# BLDC_driver_2020-06-03_09-24-41.net
KiCad netlist of a schematic drawn in EasyEDA
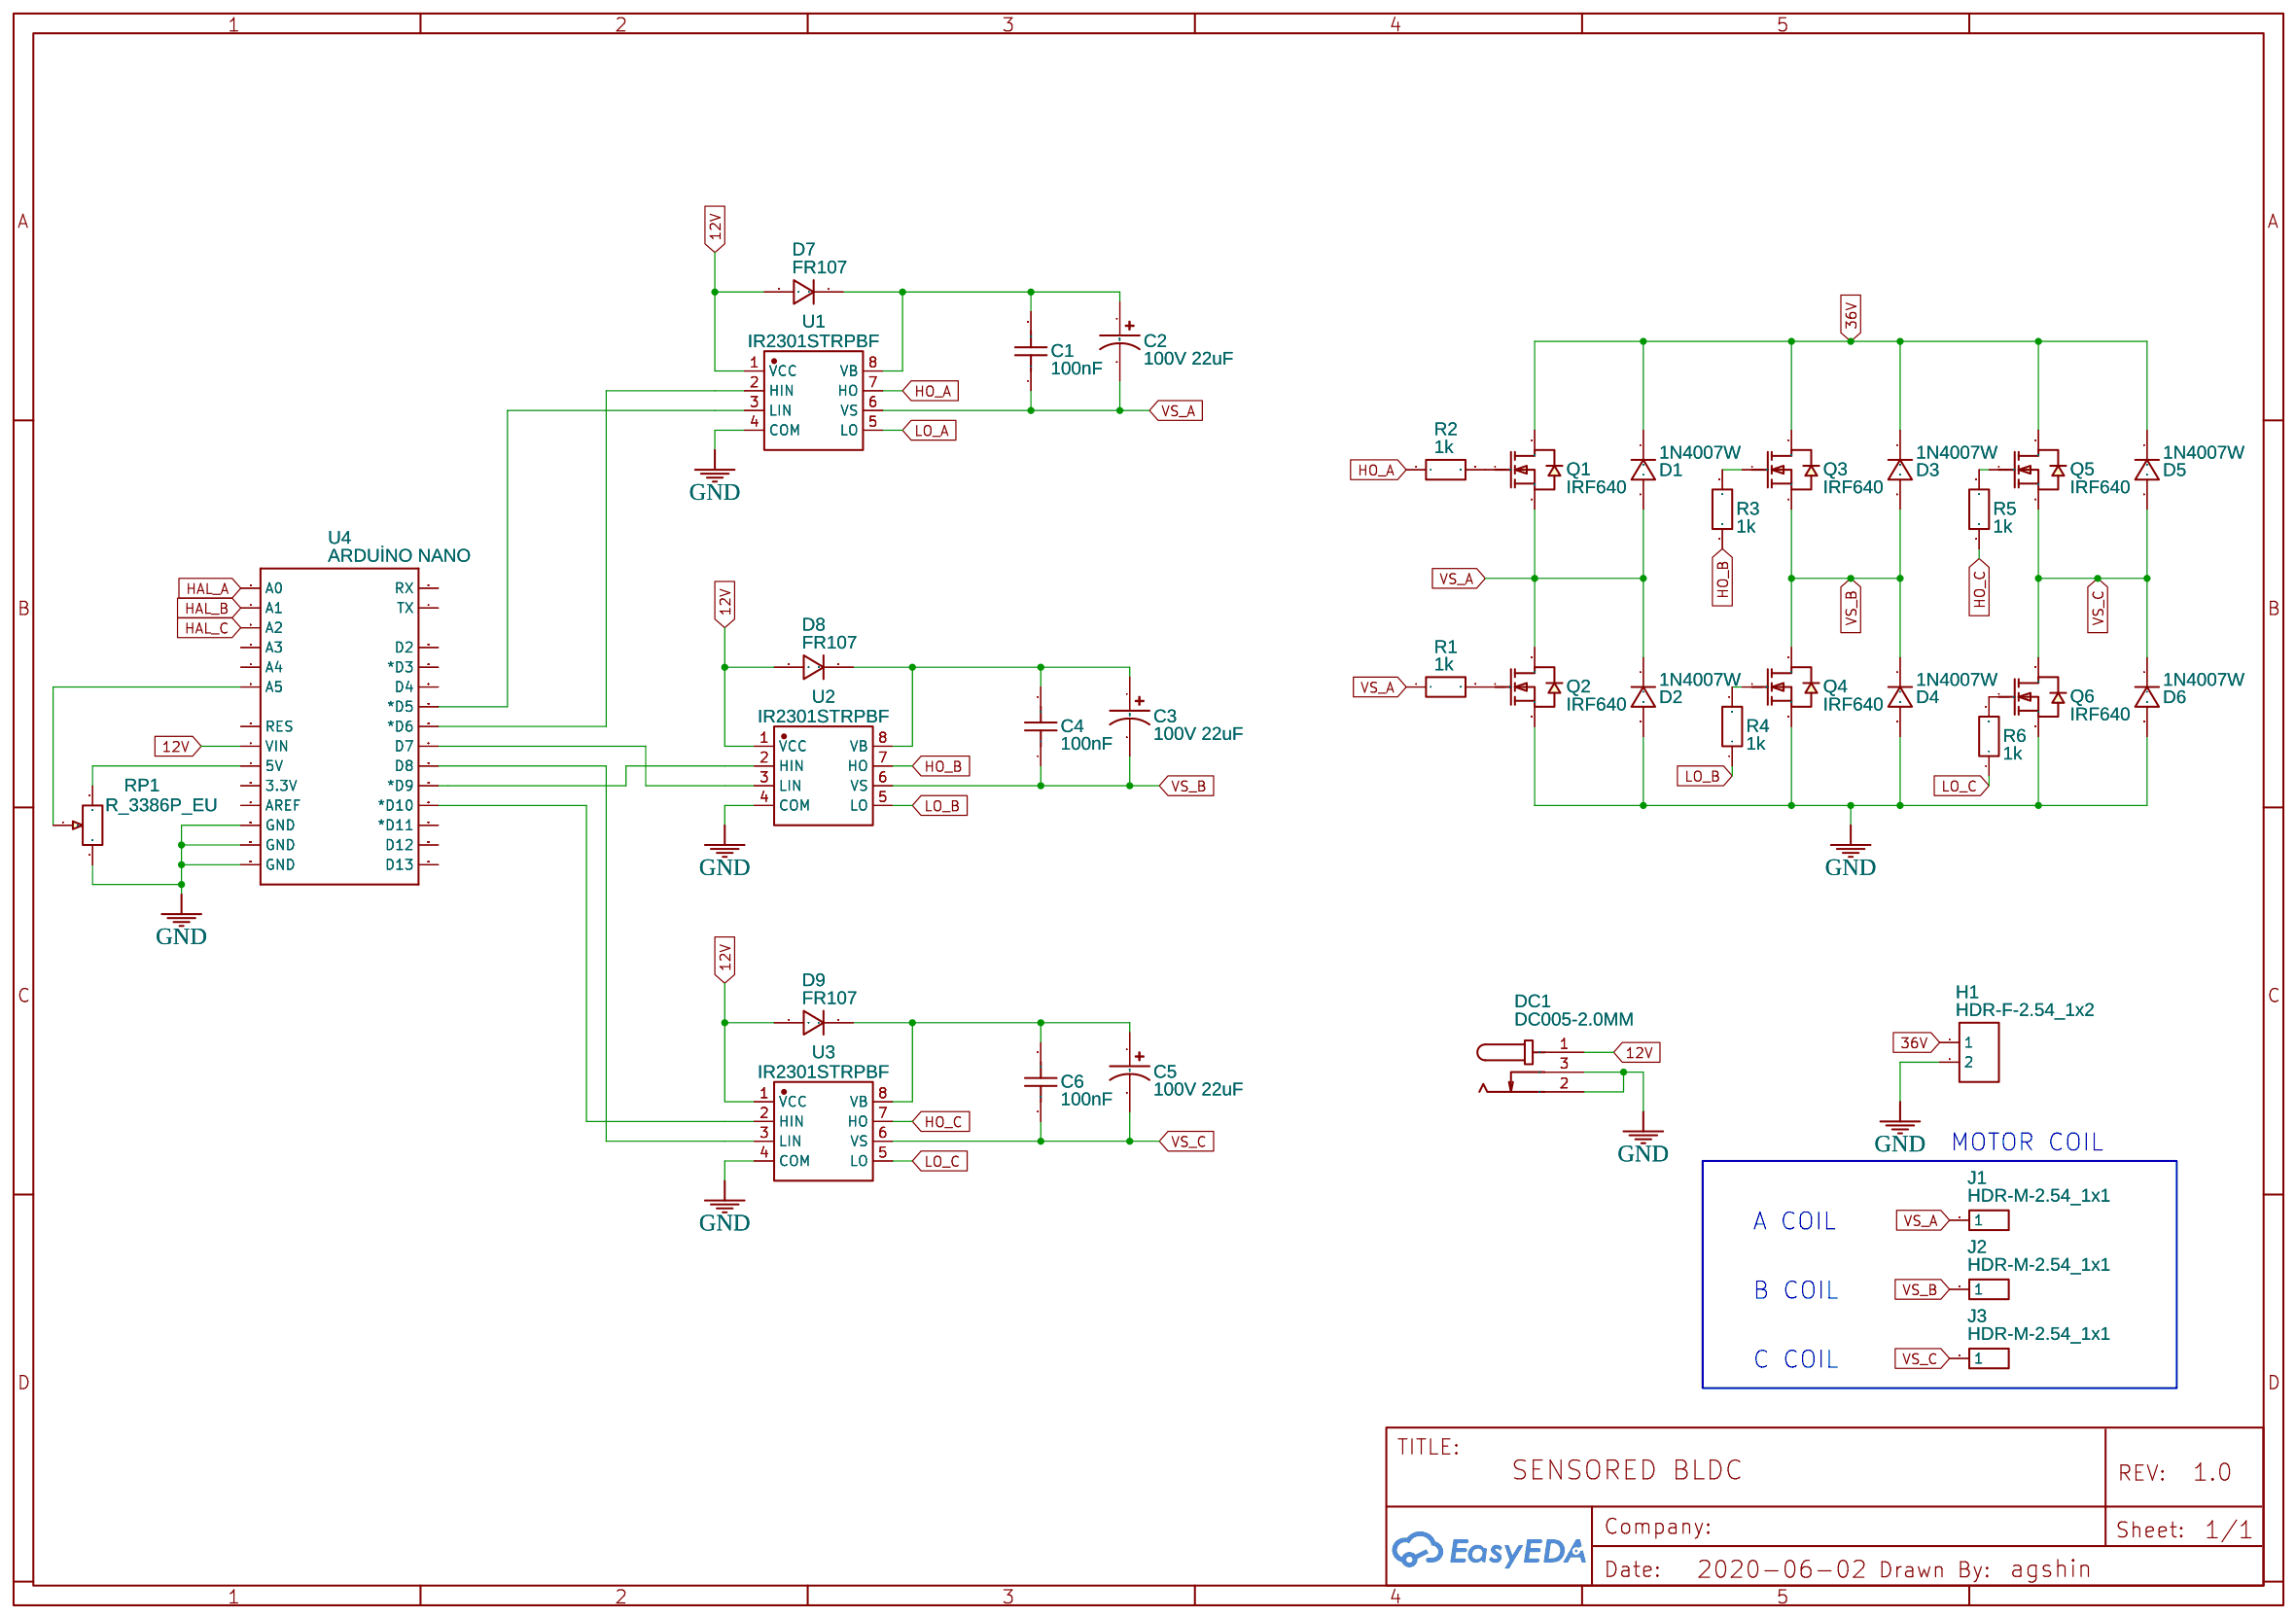
[diagram p0: schematic sheet]

(export (version "E")
  (design (tool "Eeschema 10.0.6"))
  (components
    (comp (ref "C1") (value "100nF") (libsource (lib "") (part "C_0201_US")))
    (comp (ref "C2") (value "100V 22uF") (libsource (lib "") (part "C_Tan_SMD_A_US")))
    (comp (ref "C3") (value "100V 22uF") (libsource (lib "") (part "C_Tan_SMD_A_US")))
    (comp (ref "C4") (value "100nF") (libsource (lib "") (part "C_0201_US")))
    (comp (ref "C5") (value "100V 22uF") (libsource (lib "") (part "C_Tan_SMD_A_US")))
    (comp (ref "C6") (value "100nF") (libsource (lib "") (part "C_0201_US")))
    (comp (ref "D1")
      (value "1N4007W")
      (fields (field (name "BOM_Supplier Part") "C328592"))
      (libsource (lib "") (part "1N4007W"))
    )
    (comp (ref "D2")
      (value "1N4007W")
      (fields (field (name "BOM_Supplier Part") "C328592"))
      (libsource (lib "") (part "1N4007W"))
    )
    (comp (ref "D3")
      (value "1N4007W")
      (fields (field (name "BOM_Supplier Part") "C328592"))
      (libsource (lib "") (part "1N4007W"))
    )
    (comp (ref "D4")
      (value "1N4007W")
      (fields (field (name "BOM_Supplier Part") "C328592"))
      (libsource (lib "") (part "1N4007W"))
    )
    (comp (ref "D5")
      (value "1N4007W")
      (fields (field (name "BOM_Supplier Part") "C328592"))
      (libsource (lib "") (part "1N4007W"))
    )
    (comp (ref "D6")
      (value "1N4007W")
      (fields (field (name "BOM_Supplier Part") "C328592"))
      (libsource (lib "") (part "1N4007W"))
    )
    (comp (ref "D7")
      (value "FR107")
      (fields (field (name "BOM_Manufacturer Part") "1N4007W") (field (name "BOM_Supplier Part") "C328592"))
      (libsource (lib "") (part "1N4007W_1"))
    )
    (comp (ref "D8")
      (value "FR107")
      (fields (field (name "BOM_Manufacturer Part") "1N4007W") (field (name "BOM_Supplier Part") "C328592"))
      (libsource (lib "") (part "1N4007W_1"))
    )
    (comp (ref "D9")
      (value "FR107")
      (fields (field (name "BOM_Manufacturer Part") "1N4007W") (field (name "BOM_Supplier Part") "C328592"))
      (libsource (lib "") (part "1N4007W_1"))
    )
    (comp (ref "DC1")
      (value "DC005-2.0MM")
      (fields (field (name "BOM_Supplier Part") "C111567"))
      (libsource (lib "") (part "DC005-2.0MM"))
    )
    (comp (ref "H1")
      (value "HDR-F-2.54_1x2")
      (fields (field (name "BOM_Supplier Part") "C49661"))
      (libsource (lib "") (part "HDR-F-2.54_1x2"))
    )
    (comp (ref "J1")
      (value "HDR-M-2.54_1x1")
      (fields (field (name "BOM_Supplier Part") "C81276"))
      (libsource (lib "") (part "HDR-M-2.54_1x1"))
    )
    (comp (ref "J2")
      (value "HDR-M-2.54_1x1")
      (fields (field (name "BOM_Supplier Part") "C81276"))
      (libsource (lib "") (part "HDR-M-2.54_1x1"))
    )
    (comp (ref "J3")
      (value "HDR-M-2.54_1x1")
      (fields (field (name "BOM_Supplier Part") "C81276"))
      (libsource (lib "") (part "HDR-M-2.54_1x1"))
    )
    (comp (ref "Q1")
      (value "IRF640")
      (fields (field (name "BOM_Manufacturer Part") "2N7002,215") (field (name "BOM_Supplier Part") "C65189"))
      (libsource (lib "") (part "2N7002"))
    )
    (comp (ref "Q2")
      (value "IRF640")
      (fields (field (name "BOM_Manufacturer Part") "2N7002,215") (field (name "BOM_Supplier Part") "C65189"))
      (libsource (lib "") (part "2N7002"))
    )
    (comp (ref "Q3")
      (value "IRF640")
      (fields (field (name "BOM_Manufacturer Part") "2N7002,215") (field (name "BOM_Supplier Part") "C65189"))
      (libsource (lib "") (part "2N7002"))
    )
    (comp (ref "Q4")
      (value "IRF640")
      (fields (field (name "BOM_Manufacturer Part") "2N7002,215") (field (name "BOM_Supplier Part") "C65189"))
      (libsource (lib "") (part "2N7002"))
    )
    (comp (ref "Q5")
      (value "IRF640")
      (fields (field (name "BOM_Manufacturer Part") "2N7002,215") (field (name "BOM_Supplier Part") "C65189"))
      (libsource (lib "") (part "2N7002"))
    )
    (comp (ref "Q6")
      (value "IRF640")
      (fields (field (name "BOM_Manufacturer Part") "2N7002,215") (field (name "BOM_Supplier Part") "C65189"))
      (libsource (lib "") (part "2N7002"))
    )
    (comp (ref "R1") (value "1k") (libsource (lib "") (part "R_0201_EU_1")))
    (comp (ref "R2") (value "1k") (libsource (lib "") (part "R_0201_EU_1")))
    (comp (ref "R3") (value "1k") (libsource (lib "") (part "R_0201_EU")))
    (comp (ref "R4") (value "1k") (libsource (lib "") (part "R_0201_EU")))
    (comp (ref "R5") (value "1k") (libsource (lib "") (part "R_0201_EU")))
    (comp (ref "R6") (value "1k") (libsource (lib "") (part "R_0201_EU")))
    (comp (ref "RP1") (value "R_3386P_EU") (libsource (lib "") (part "R_3386P_EU")))
    (comp (ref "U1")
      (value "IR2301STRPBF")
      (fields (field (name "BOM_Supplier Part") "C413500"))
      (libsource (lib "") (part "IR2301STRPBF"))
    )
    (comp (ref "U2")
      (value "IR2301STRPBF")
      (fields (field (name "BOM_Supplier Part") "C413500"))
      (libsource (lib "") (part "IR2301STRPBF"))
    )
    (comp (ref "U3")
      (value "IR2301STRPBF")
      (fields (field (name "BOM_Supplier Part") "C413500"))
      (libsource (lib "") (part "IR2301STRPBF"))
    )
    (comp (ref "U4") (value "ARDUİNO NANO") (libsource (lib "") (part "ARDUINO_SHIELDNO_SILK")))
  )
  (nets
    (net (code "1") (name "12V") (class "Default")
      (node (ref "D7") (pin "2") (pinfunction "2_2") (pintype "unspecified"))
      (node (ref "D8") (pin "2") (pinfunction "2_2") (pintype "unspecified"))
      (node (ref "D9") (pin "2") (pinfunction "2_2") (pintype "unspecified"))
      (node (ref "DC1") (pin "1") (pinfunction "1_1") (pintype "unspecified"))
      (node (ref "U1") (pin "1") (pinfunction "VCC_1") (pintype "unspecified"))
      (node (ref "U2") (pin "1") (pinfunction "VCC_1") (pintype "unspecified"))
      (node (ref "U3") (pin "1") (pinfunction "VCC_1") (pintype "unspecified"))
      (node (ref "U4") (pin "VIN") (pinfunction "VIN_VIN") (pintype "unspecified"))
    )
    (net (code "2") (name "36V") (class "Default")
      (node (ref "D1") (pin "1") (pinfunction "1_1") (pintype "unspecified"))
      (node (ref "D3") (pin "1") (pinfunction "1_1") (pintype "unspecified"))
      (node (ref "D5") (pin "1") (pinfunction "1_1") (pintype "unspecified"))
      (node (ref "H1") (pin "1") (pinfunction "1_1") (pintype "input"))
      (node (ref "Q1") (pin "3") (pinfunction "D_3") (pintype "unspecified"))
      (node (ref "Q3") (pin "3") (pinfunction "D_3") (pintype "unspecified"))
      (node (ref "Q5") (pin "3") (pinfunction "D_3") (pintype "unspecified"))
    )
    (net (code "3") (name "GND") (class "Default")
      (node (ref "D2") (pin "2") (pinfunction "2_2") (pintype "unspecified"))
      (node (ref "D4") (pin "2") (pinfunction "2_2") (pintype "unspecified"))
      (node (ref "D6") (pin "2") (pinfunction "2_2") (pintype "unspecified"))
      (node (ref "DC1") (pin "2") (pinfunction "2_2") (pintype "unspecified"))
      (node (ref "DC1") (pin "3") (pinfunction "3_3") (pintype "unspecified"))
      (node (ref "H1") (pin "2") (pinfunction "2_2") (pintype "input"))
      (node (ref "Q2") (pin "2") (pinfunction "S_2") (pintype "unspecified"))
      (node (ref "Q4") (pin "2") (pinfunction "S_2") (pintype "unspecified"))
      (node (ref "Q6") (pin "2") (pinfunction "S_2") (pintype "unspecified"))
      (node (ref "RP1") (pin "1") (pinfunction "1_1") (pintype "input"))
      (node (ref "U1") (pin "4") (pinfunction "COM_4") (pintype "unspecified"))
      (node (ref "U2") (pin "4") (pinfunction "COM_4") (pintype "unspecified"))
      (node (ref "U3") (pin "4") (pinfunction "COM_4") (pintype "unspecified"))
      (node (ref "U4") (pin "GND@0") (pinfunction "GND_GND@0") (pintype "unspecified"))
      (node (ref "U4") (pin "GND@1") (pinfunction "GND_GND@1") (pintype "unspecified"))
      (node (ref "U4") (pin "GND@2") (pinfunction "GND_GND@2") (pintype "unspecified"))
    )
    (net (code "4") (name "HAL_A") (class "Default")
      (node (ref "U4") (pin "A0") (pinfunction "A0_A0") (pintype "unspecified"))
    )
    (net (code "5") (name "HAL_B") (class "Default")
      (node (ref "U4") (pin "A1") (pinfunction "A1_A1") (pintype "unspecified"))
    )
    (net (code "6") (name "HAL_C") (class "Default")
      (node (ref "U4") (pin "A2") (pinfunction "A2_A2") (pintype "unspecified"))
    )
    (net (code "7") (name "HO_A") (class "Default")
      (node (ref "R2") (pin "1") (pinfunction "1_1") (pintype "unspecified"))
      (node (ref "U1") (pin "7") (pinfunction "HO_7") (pintype "unspecified"))
    )
    (net (code "8") (name "HO_B") (class "Default")
      (node (ref "R3") (pin "1") (pinfunction "1_1") (pintype "unspecified"))
      (node (ref "U2") (pin "7") (pinfunction "HO_7") (pintype "unspecified"))
    )
    (net (code "9") (name "HO_C") (class "Default")
      (node (ref "R5") (pin "1") (pinfunction "1_1") (pintype "unspecified"))
      (node (ref "U3") (pin "7") (pinfunction "HO_7") (pintype "unspecified"))
    )
    (net (code "10") (name "LO_A") (class "Default")
      (node (ref "U1") (pin "5") (pinfunction "LO_5") (pintype "unspecified"))
    )
    (net (code "11") (name "LO_B") (class "Default")
      (node (ref "R4") (pin "1") (pinfunction "1_1") (pintype "unspecified"))
      (node (ref "U2") (pin "5") (pinfunction "LO_5") (pintype "unspecified"))
    )
    (net (code "12") (name "LO_C") (class "Default")
      (node (ref "R6") (pin "1") (pinfunction "1_1") (pintype "unspecified"))
      (node (ref "U3") (pin "5") (pinfunction "LO_5") (pintype "unspecified"))
    )
    (net (code "13") (name "Net-(Q1-G)") (class "Default")
      (node (ref "Q1") (pin "1") (pinfunction "G_1") (pintype "unspecified"))
      (node (ref "R2") (pin "2") (pinfunction "2_2") (pintype "unspecified"))
    )
    (net (code "14") (name "Net-(Q2-G)") (class "Default")
      (node (ref "Q2") (pin "1") (pinfunction "G_1") (pintype "unspecified"))
      (node (ref "R1") (pin "2") (pinfunction "2_2") (pintype "unspecified"))
    )
    (net (code "15") (name "Net-(Q3-G)") (class "Default")
      (node (ref "Q3") (pin "1") (pinfunction "G_1") (pintype "unspecified"))
      (node (ref "R3") (pin "2") (pinfunction "2_2") (pintype "unspecified"))
    )
    (net (code "16") (name "Net-(Q4-G)") (class "Default")
      (node (ref "Q4") (pin "1") (pinfunction "G_1") (pintype "unspecified"))
      (node (ref "R4") (pin "2") (pinfunction "2_2") (pintype "unspecified"))
    )
    (net (code "17") (name "Net-(Q5-G)") (class "Default")
      (node (ref "Q5") (pin "1") (pinfunction "G_1") (pintype "unspecified"))
      (node (ref "R5") (pin "2") (pinfunction "2_2") (pintype "unspecified"))
    )
    (net (code "18") (name "Net-(Q6-G)") (class "Default")
      (node (ref "Q6") (pin "1") (pinfunction "G_1") (pintype "unspecified"))
      (node (ref "R6") (pin "2") (pinfunction "2_2") (pintype "unspecified"))
    )
    (net (code "19") (name "Net-(RP1-Pad2)") (class "Default")
      (node (ref "RP1") (pin "2") (pinfunction "2_2") (pintype "input"))
      (node (ref "U4") (pin "A5") (pinfunction "A5_A5") (pintype "unspecified"))
    )
    (net (code "20") (name "Net-(RP1-Pad3)") (class "Default")
      (node (ref "RP1") (pin "3") (pinfunction "3_3") (pintype "input"))
      (node (ref "U4") (pin "5V") (pinfunction "5V_5V") (pintype "unspecified"))
    )
    (net (code "21") (name "Net-(U1-HIN)") (class "Default")
      (node (ref "U1") (pin "2") (pinfunction "HIN_2") (pintype "unspecified"))
      (node (ref "U4") (pin "D6") (pinfunction "*D6_D6") (pintype "unspecified"))
    )
    (net (code "22") (name "Net-(U1-LIN)") (class "Default")
      (node (ref "U1") (pin "3") (pinfunction "LIN_3") (pintype "unspecified"))
      (node (ref "U4") (pin "D5") (pinfunction "*D5_D5") (pintype "unspecified"))
    )
    (net (code "23") (name "Net-(U1-VB)") (class "Default")
      (node (ref "C1") (pin "2") (pinfunction "2_2") (pintype "unspecified"))
      (node (ref "C2") (pin "1") (pinfunction "1_1") (pintype "unspecified"))
      (node (ref "D7") (pin "1") (pinfunction "1_1") (pintype "unspecified"))
      (node (ref "U1") (pin "8") (pinfunction "VB_8") (pintype "unspecified"))
    )
    (net (code "24") (name "Net-(U2-HIN)") (class "Default")
      (node (ref "U2") (pin "2") (pinfunction "HIN_2") (pintype "unspecified"))
      (node (ref "U4") (pin "D9") (pinfunction "*D9_D9") (pintype "unspecified"))
    )
    (net (code "25") (name "Net-(U2-LIN)") (class "Default")
      (node (ref "U2") (pin "3") (pinfunction "LIN_3") (pintype "unspecified"))
      (node (ref "U4") (pin "D7") (pinfunction "D7_D7") (pintype "unspecified"))
    )
    (net (code "26") (name "Net-(U2-VB)") (class "Default")
      (node (ref "C3") (pin "1") (pinfunction "1_1") (pintype "unspecified"))
      (node (ref "C4") (pin "2") (pinfunction "2_2") (pintype "unspecified"))
      (node (ref "D8") (pin "1") (pinfunction "1_1") (pintype "unspecified"))
      (node (ref "U2") (pin "8") (pinfunction "VB_8") (pintype "unspecified"))
    )
    (net (code "27") (name "Net-(U3-HIN)") (class "Default")
      (node (ref "U3") (pin "2") (pinfunction "HIN_2") (pintype "unspecified"))
      (node (ref "U4") (pin "D10") (pinfunction "*D10_D10") (pintype "unspecified"))
    )
    (net (code "28") (name "Net-(U3-LIN)") (class "Default")
      (node (ref "U3") (pin "3") (pinfunction "LIN_3") (pintype "unspecified"))
      (node (ref "U4") (pin "D8") (pinfunction "D8_D8") (pintype "unspecified"))
    )
    (net (code "29") (name "Net-(U3-VB)") (class "Default")
      (node (ref "C5") (pin "1") (pinfunction "1_1") (pintype "unspecified"))
      (node (ref "C6") (pin "2") (pinfunction "2_2") (pintype "unspecified"))
      (node (ref "D9") (pin "1") (pinfunction "1_1") (pintype "unspecified"))
      (node (ref "U3") (pin "8") (pinfunction "VB_8") (pintype "unspecified"))
    )
    (net (code "30") (name "VS_A") (class "Default")
      (node (ref "C1") (pin "1") (pinfunction "1_1") (pintype "unspecified"))
      (node (ref "C2") (pin "2") (pinfunction "2_2") (pintype "unspecified"))
      (node (ref "D1") (pin "2") (pinfunction "2_2") (pintype "unspecified"))
      (node (ref "D2") (pin "1") (pinfunction "1_1") (pintype "unspecified"))
      (node (ref "J1") (pin "1") (pinfunction "1_1") (pintype "input"))
      (node (ref "Q1") (pin "2") (pinfunction "S_2") (pintype "unspecified"))
      (node (ref "Q2") (pin "3") (pinfunction "D_3") (pintype "unspecified"))
      (node (ref "R1") (pin "1") (pinfunction "1_1") (pintype "unspecified"))
      (node (ref "U1") (pin "6") (pinfunction "VS_6") (pintype "unspecified"))
    )
    (net (code "31") (name "VS_B") (class "Default")
      (node (ref "C3") (pin "2") (pinfunction "2_2") (pintype "unspecified"))
      (node (ref "C4") (pin "1") (pinfunction "1_1") (pintype "unspecified"))
      (node (ref "D3") (pin "2") (pinfunction "2_2") (pintype "unspecified"))
      (node (ref "D4") (pin "1") (pinfunction "1_1") (pintype "unspecified"))
      (node (ref "J2") (pin "1") (pinfunction "1_1") (pintype "input"))
      (node (ref "Q3") (pin "2") (pinfunction "S_2") (pintype "unspecified"))
      (node (ref "Q4") (pin "3") (pinfunction "D_3") (pintype "unspecified"))
      (node (ref "U2") (pin "6") (pinfunction "VS_6") (pintype "unspecified"))
    )
    (net (code "32") (name "VS_C") (class "Default")
      (node (ref "C5") (pin "2") (pinfunction "2_2") (pintype "unspecified"))
      (node (ref "C6") (pin "1") (pinfunction "1_1") (pintype "unspecified"))
      (node (ref "D5") (pin "2") (pinfunction "2_2") (pintype "unspecified"))
      (node (ref "D6") (pin "1") (pinfunction "1_1") (pintype "unspecified"))
      (node (ref "J3") (pin "1") (pinfunction "1_1") (pintype "input"))
      (node (ref "Q5") (pin "2") (pinfunction "S_2") (pintype "unspecified"))
      (node (ref "Q6") (pin "3") (pinfunction "D_3") (pintype "unspecified"))
      (node (ref "U3") (pin "6") (pinfunction "VS_6") (pintype "unspecified"))
    )
    (net (code "33") (name "unconnected-(U4-*D3-PadD3)") (class "Default")
      (node (ref "U4") (pin "D3") (pinfunction "*D3_D3") (pintype "unspecified"))
    )
    (net (code "34") (name "unconnected-(U4-*D11-PadD11)") (class "Default")
      (node (ref "U4") (pin "D11") (pinfunction "*D11_D11") (pintype "unspecified"))
    )
    (net (code "35") (name "unconnected-(U4-Pad3.3V)") (class "Default")
      (node (ref "U4") (pin "3.3V") (pinfunction "3.3V_3.3V") (pintype "unspecified"))
    )
    (net (code "36") (name "unconnected-(U4-PadA3)") (class "Default")
      (node (ref "U4") (pin "A3") (pinfunction "A3_A3") (pintype "unspecified"))
    )
    (net (code "37") (name "unconnected-(U4-PadA4)") (class "Default")
      (node (ref "U4") (pin "A4") (pinfunction "A4_A4") (pintype "unspecified"))
    )
    (net (code "38") (name "unconnected-(U4-PadAREF)") (class "Default")
      (node (ref "U4") (pin "AREF") (pinfunction "AREF_AREF") (pintype "unspecified"))
    )
    (net (code "39") (name "unconnected-(U4-PadD2)") (class "Default")
      (node (ref "U4") (pin "D2") (pinfunction "D2_D2") (pintype "unspecified"))
    )
    (net (code "40") (name "unconnected-(U4-PadD4)") (class "Default")
      (node (ref "U4") (pin "D4") (pinfunction "D4_D4") (pintype "unspecified"))
    )
    (net (code "41") (name "unconnected-(U4-PadD12)") (class "Default")
      (node (ref "U4") (pin "D12") (pinfunction "D12_D12") (pintype "unspecified"))
    )
    (net (code "42") (name "unconnected-(U4-PadD13)") (class "Default")
      (node (ref "U4") (pin "D13") (pinfunction "D13_D13") (pintype "unspecified"))
    )
    (net (code "43") (name "unconnected-(U4-PadRES)") (class "Default")
      (node (ref "U4") (pin "RES") (pinfunction "RES_RES") (pintype "unspecified"))
    )
    (net (code "44") (name "unconnected-(U4-PadRX)") (class "Default")
      (node (ref "U4") (pin "RX") (pinfunction "RX_RX") (pintype "unspecified"))
    )
    (net (code "45") (name "unconnected-(U4-PadTX)") (class "Default")
      (node (ref "U4") (pin "TX") (pinfunction "TX_TX") (pintype "unspecified"))
    )
  )
)
